# power.net
KiCad netlist of a schematic drawn in Altium Designer
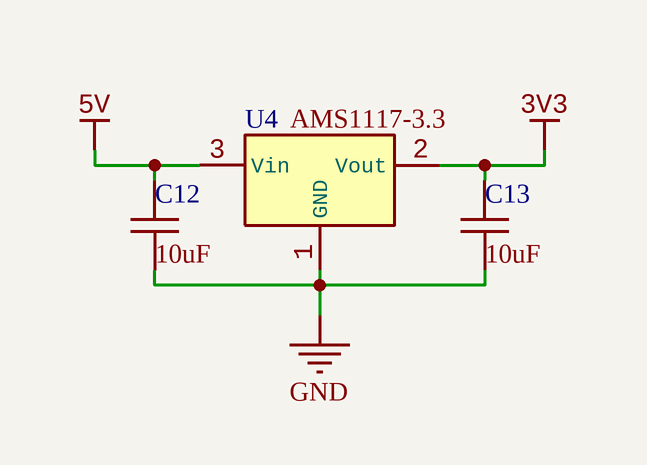
[diagram p0: power.SchDoc]

(export (version "E")
  (design (tool "Eeschema 10.0.6"))
  (components
    (comp (ref "C12") (value "10uF") (footprint "C_0805") (libsource (lib "STM32") (part "C_MLCC")))
    (comp (ref "C13") (value "10uF") (footprint "C_0805") (libsource (lib "STM32") (part "C_MLCC")))
    (comp (ref "U4")
      (value "AMS1117-3.3")
      (footprint "SOT-89-3P")
      (libsource (lib "STM32") (part "AMS1117-3.3"))
    )
  )
  (nets
    (net (code "1") (name "3V3") (class "Default")
      (node (ref "C13") (pin "1") (pinfunction "1_1") (pintype "passive"))
      (node (ref "U4") (pin "2") (pinfunction "Vout_2") (pintype "passive"))
    )
    (net (code "2") (name "5V") (class "Default")
      (node (ref "C12") (pin "1") (pinfunction "1_1") (pintype "passive"))
      (node (ref "U4") (pin "3") (pinfunction "Vin_3") (pintype "passive"))
    )
    (net (code "3") (name "GND") (class "Default")
      (node (ref "C12") (pin "2") (pinfunction "2_2") (pintype "passive"))
      (node (ref "C13") (pin "2") (pinfunction "2_2") (pintype "passive"))
      (node (ref "U4") (pin "1") (pinfunction "GND_1") (pintype "passive"))
    )
  )
)
